# MiniLab.net
KiCad netlist of a schematic drawn in EAGLE
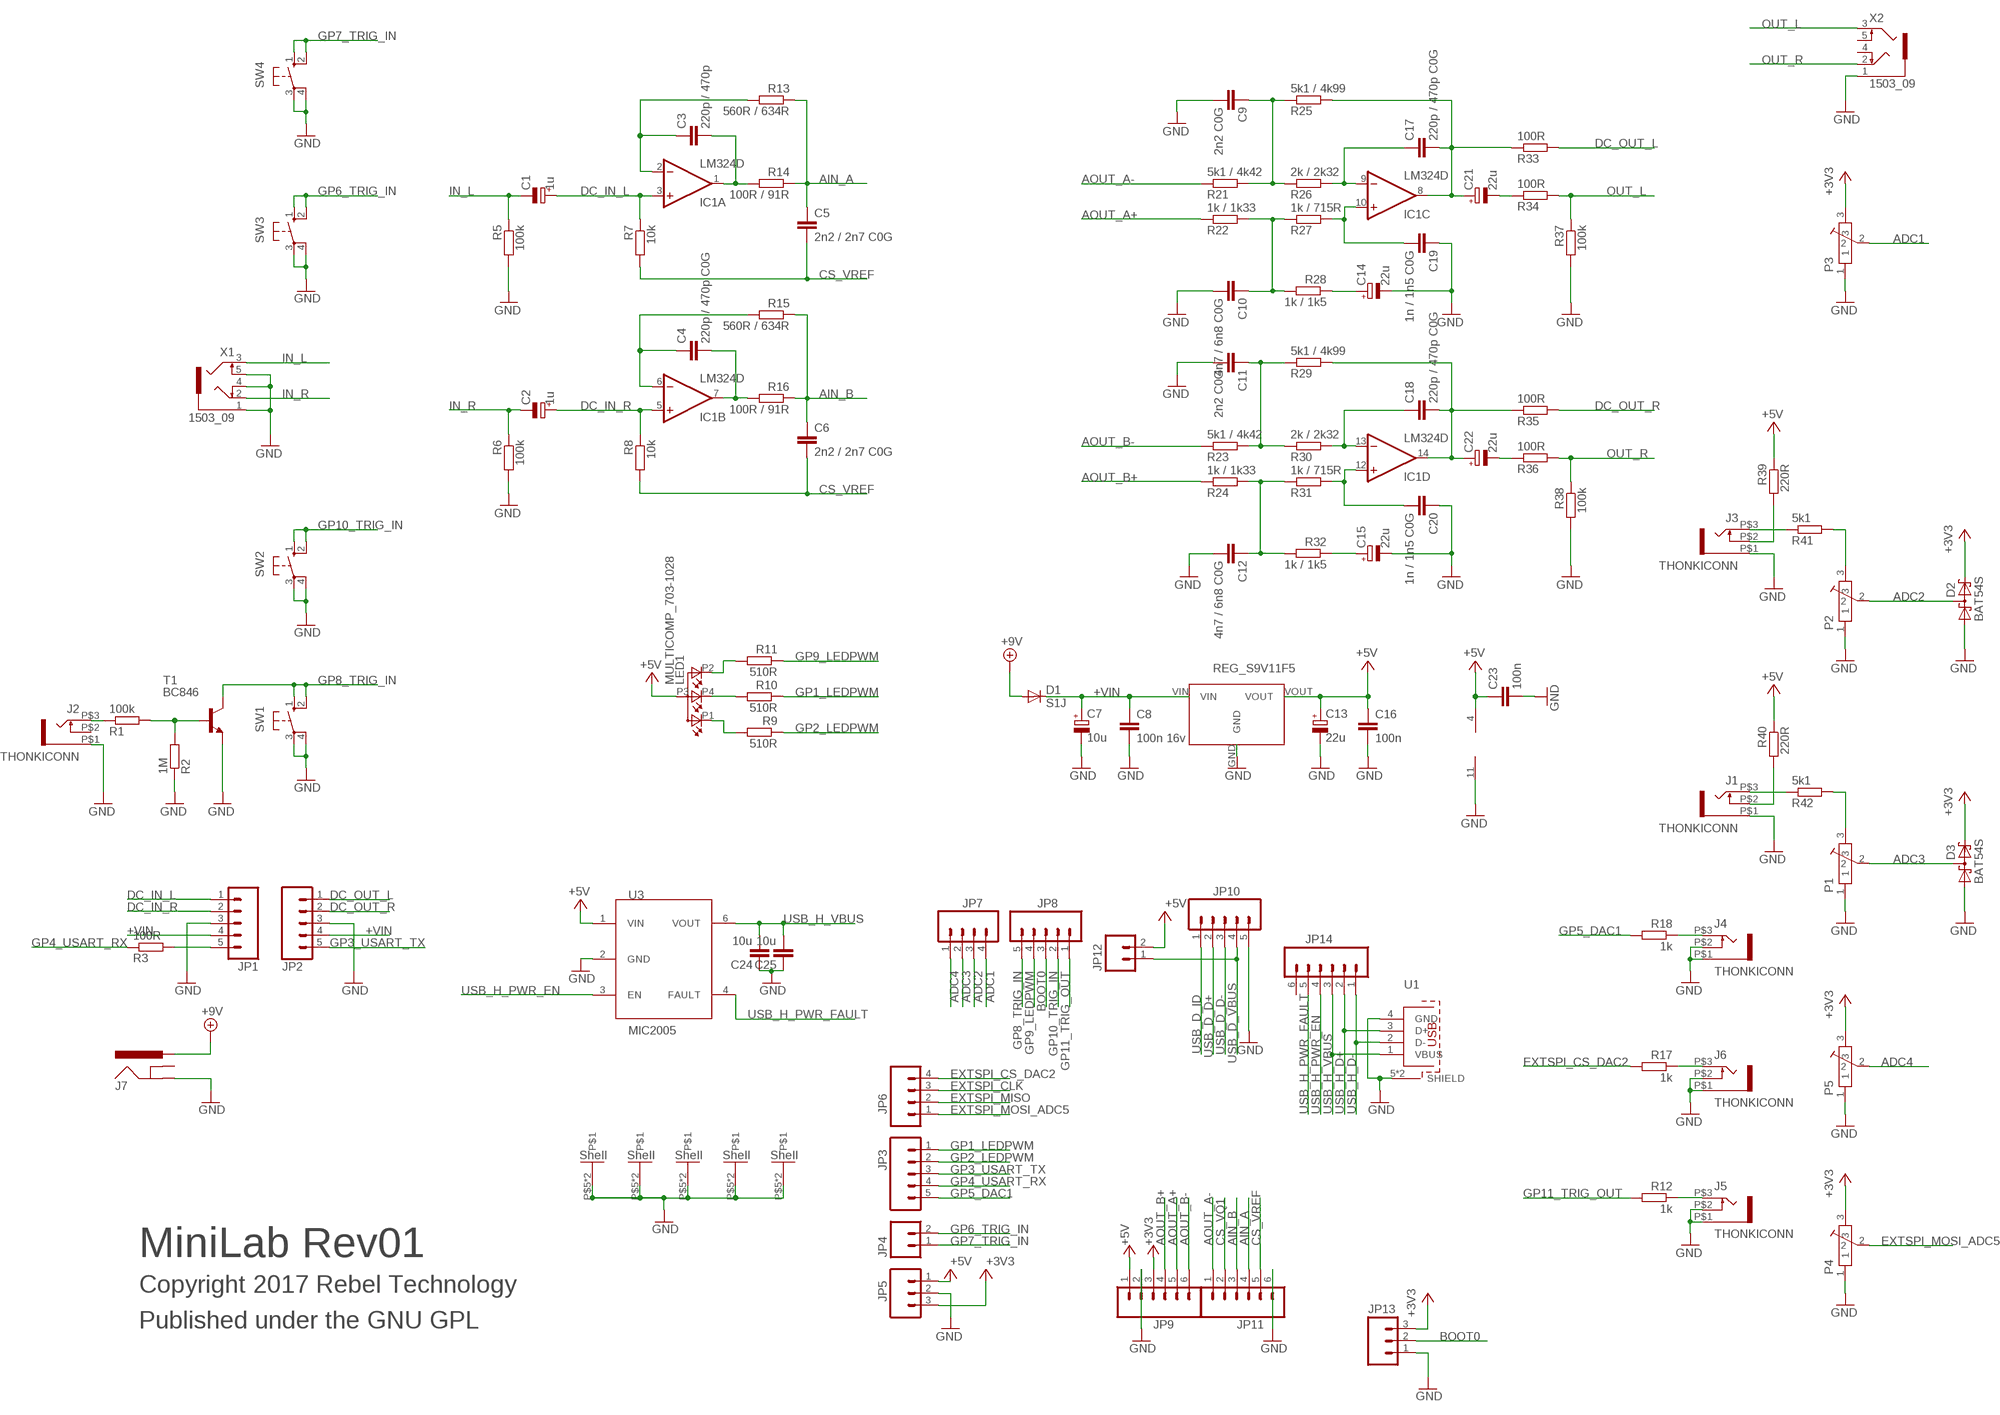
[diagram p0: schematic, sheet 1]

(export (version "E")
  (design (tool "Eeschema 10.0.6"))
  (components
    (comp (ref "C1")
      (value "1u")
      (footprint "eagle-import:153CLV-0405")
      (libsource (lib "eagle-import") (part "CPOL-EU153CLV-0405"))
    )
    (comp (ref "C2")
      (value "1u")
      (footprint "eagle-import:153CLV-0405")
      (libsource (lib "eagle-import") (part "CPOL-EU153CLV-0405"))
    )
    (comp (ref "C3")
      (value "220p / 470p")
      (footprint "eagle-import:C0603")
      (libsource (lib "eagle-import") (part "resistor_C-EUC0603"))
    )
    (comp (ref "C4")
      (value "220p / 470p C0G")
      (footprint "eagle-import:C0603")
      (libsource (lib "eagle-import") (part "resistor_C-EUC0603"))
    )
    (comp (ref "C5")
      (value "2n2 / 2n7 C0G")
      (footprint "eagle-import:C0603")
      (libsource (lib "eagle-import") (part "resistor_C-EUC0603"))
    )
    (comp (ref "C6")
      (value "2n2 / 2n7 C0G")
      (footprint "eagle-import:C0603")
      (libsource (lib "eagle-import") (part "resistor_C-EUC0603"))
    )
    (comp (ref "C7")
      (value "10u")
      (footprint "eagle-import:153CLV-0405")
      (libsource (lib "eagle-import") (part "CPOL-EU153CLV-0405"))
    )
    (comp (ref "C8")
      (value "100n 16v")
      (footprint "eagle-import:C0603")
      (libsource (lib "eagle-import") (part "C-EUC0603"))
    )
    (comp (ref "C9")
      (value "2n2 C0G")
      (footprint "eagle-import:C0603")
      (libsource (lib "eagle-import") (part "resistor_C-EUC0603"))
    )
    (comp (ref "C10")
      (value "4n7 / 6n8 C0G")
      (footprint "eagle-import:C0603")
      (libsource (lib "eagle-import") (part "resistor_C-EUC0603"))
    )
    (comp (ref "C11")
      (value "2n2 C0G")
      (footprint "eagle-import:C0603")
      (libsource (lib "eagle-import") (part "resistor_C-EUC0603"))
    )
    (comp (ref "C12")
      (value "4n7 / 6n8 C0G")
      (footprint "eagle-import:C0603")
      (libsource (lib "eagle-import") (part "resistor_C-EUC0603"))
    )
    (comp (ref "C13")
      (value "22u")
      (footprint "eagle-import:CPOL-5")
      (libsource (lib "eagle-import") (part "CPOL-EU153CLV-0505"))
    )
    (comp (ref "C14")
      (value "22u")
      (footprint "eagle-import:CPOL-5")
      (libsource (lib "eagle-import") (part "CPOL-EU153CLV-0505"))
    )
    (comp (ref "C15")
      (value "22u")
      (footprint "eagle-import:CPOL-5")
      (libsource (lib "eagle-import") (part "CPOL-EU153CLV-0505"))
    )
    (comp (ref "C16")
      (value "100n")
      (footprint "eagle-import:C0603")
      (libsource (lib "eagle-import") (part "C-EUC0603"))
    )
    (comp (ref "C17")
      (value "220p / 470p C0G")
      (footprint "eagle-import:C0603")
      (libsource (lib "eagle-import") (part "resistor_C-EUC0603"))
    )
    (comp (ref "C18")
      (value "220p / 470p C0G")
      (footprint "eagle-import:C0603")
      (libsource (lib "eagle-import") (part "resistor_C-EUC0603"))
    )
    (comp (ref "C19")
      (value "1n / 1n5 C0G")
      (footprint "eagle-import:C0603")
      (libsource (lib "eagle-import") (part "resistor_C-EUC0603"))
    )
    (comp (ref "C20")
      (value "1n / 1n5 C0G")
      (footprint "eagle-import:C0603")
      (libsource (lib "eagle-import") (part "resistor_C-EUC0603"))
    )
    (comp (ref "C21")
      (value "22u")
      (footprint "eagle-import:CPOL-5")
      (libsource (lib "eagle-import") (part "CPOL-EU153CLV-0505"))
    )
    (comp (ref "C22")
      (value "22u")
      (footprint "eagle-import:CPOL-5")
      (libsource (lib "eagle-import") (part "CPOL-EU153CLV-0505"))
    )
    (comp (ref "C23")
      (value "100n")
      (footprint "eagle-import:C0603")
      (libsource (lib "eagle-import") (part "resistor_C-EUC0603"))
    )
    (comp (ref "C24")
      (value "10u")
      (footprint "eagle-import:C0603")
      (libsource (lib "eagle-import") (part "resistor_C-EUC0603"))
    )
    (comp (ref "C25")
      (value "10u")
      (footprint "eagle-import:C0603")
      (libsource (lib "eagle-import") (part "resistor_C-EUC0603"))
    )
    (comp (ref "D1")
      (value "S1J")
      (footprint "eagle-import:SMA-DIODE")
      (libsource (lib "eagle-import") (part "DIODESMA"))
    )
    (comp (ref "D2")
      (value "BAT54S")
      (footprint "eagle-import:SOT23")
      (libsource (lib "eagle-import") (part "BAT54S"))
    )
    (comp (ref "D3")
      (value "BAT54S")
      (footprint "eagle-import:SOT23")
      (libsource (lib "eagle-import") (part "BAT54S"))
    )
    (comp (ref "IC1")
      (value "LM324D")
      (footprint "eagle-import:SO14")
      (libsource (lib "eagle-import") (part "LM324D"))
    )
    (comp (ref "J1")
      (value "THONKICONN")
      (footprint "eagle-import:THONKICONN")
      (libsource (lib "eagle-import") (part "THONKICONN"))
    )
    (comp (ref "J2")
      (value "THONKICONN")
      (footprint "eagle-import:THONKICONN")
      (libsource (lib "eagle-import") (part "THONKICONN"))
    )
    (comp (ref "J3")
      (value "THONKICONN")
      (footprint "eagle-import:THONKICONN")
      (libsource (lib "eagle-import") (part "THONKICONN"))
    )
    (comp (ref "J4")
      (value "THONKICONN")
      (footprint "eagle-import:THONKICONN")
      (libsource (lib "eagle-import") (part "THONKICONN"))
    )
    (comp (ref "J5")
      (value "THONKICONN")
      (footprint "eagle-import:THONKICONN")
      (libsource (lib "eagle-import") (part "THONKICONN"))
    )
    (comp (ref "J6")
      (value "THONKICONN")
      (footprint "eagle-import:THONKICONN")
      (libsource (lib "eagle-import") (part "THONKICONN"))
    )
    (comp (ref "J7")
      (value "POWER_JACKPTH")
      (footprint "eagle-import:POWER_JACK_PTH")
      (libsource (lib "eagle-import") (part "POWER_JACKPTH"))
    )
    (comp (ref "JP1")
      (value "M05PTH")
      (footprint "eagle-import:1X05")
      (libsource (lib "eagle-import") (part "M05PTH"))
    )
    (comp (ref "JP2")
      (value "M05PTH")
      (footprint "eagle-import:1X05")
      (libsource (lib "eagle-import") (part "M05PTH"))
    )
    (comp (ref "JP3")
      (value "M05PTH")
      (footprint "eagle-import:1X05")
      (libsource (lib "eagle-import") (part "M05PTH"))
    )
    (comp (ref "JP4")
      (value "M02PTH")
      (footprint "eagle-import:1X02")
      (libsource (lib "eagle-import") (part "M02PTH"))
    )
    (comp (ref "JP5")
      (value "M03PTH")
      (footprint "eagle-import:1X03")
      (libsource (lib "eagle-import") (part "M03PTH"))
    )
    (comp (ref "JP6")
      (value "M04PTH")
      (footprint "eagle-import:1X04")
      (libsource (lib "eagle-import") (part "M04PTH"))
    )
    (comp (ref "JP7")
      (value "M04PTH")
      (footprint "eagle-import:1X04")
      (libsource (lib "eagle-import") (part "M04PTH"))
    )
    (comp (ref "JP8")
      (value "M05PTH")
      (footprint "eagle-import:1X05")
      (libsource (lib "eagle-import") (part "M05PTH"))
    )
    (comp (ref "JP9")
      (value "M06SIP")
      (footprint "eagle-import:1X06")
      (libsource (lib "eagle-import") (part "M06SIP"))
    )
    (comp (ref "JP10")
      (value "M05PTH")
      (footprint "eagle-import:1X05")
      (libsource (lib "eagle-import") (part "M05PTH"))
    )
    (comp (ref "JP11")
      (value "M06SIP")
      (footprint "eagle-import:1X06")
      (libsource (lib "eagle-import") (part "M06SIP"))
    )
    (comp (ref "JP12")
      (value "M02PTH")
      (footprint "eagle-import:1X02")
      (libsource (lib "eagle-import") (part "M02PTH"))
    )
    (comp (ref "JP13")
      (value "M03PTH")
      (footprint "eagle-import:1X03")
      (libsource (lib "eagle-import") (part "M03PTH"))
    )
    (comp (ref "JP14")
      (value "M06SIP")
      (footprint "eagle-import:1X06")
      (libsource (lib "eagle-import") (part "M06SIP"))
    )
    (comp (ref "LED1")
      (value "MULTICOMP_703-1028")
      (footprint "eagle-import:RGB-LED-703-1028")
      (libsource (lib "eagle-import") (part "MULTICOMP_703-1028"))
    )
    (comp (ref "P1")
      (value "POT-ALPS-RK09L1140")
      (footprint "eagle-import:POT-ALPS-RK09L1140")
      (libsource (lib "eagle-import") (part "POT-ALPS-RK09L1140"))
    )
    (comp (ref "P2")
      (value "POT-ALPS-RK09L1140")
      (footprint "eagle-import:POT-ALPS-RK09L1140")
      (libsource (lib "eagle-import") (part "POT-ALPS-RK09L1140"))
    )
    (comp (ref "P3")
      (value "POT-ALPS-RK09L1140")
      (footprint "eagle-import:POT-ALPS-RK09L1140")
      (libsource (lib "eagle-import") (part "POT-ALPS-RK09L1140"))
    )
    (comp (ref "P4")
      (value "POT-ALPS-RK09L1140")
      (footprint "eagle-import:POT-ALPS-RK09L1140")
      (libsource (lib "eagle-import") (part "POT-ALPS-RK09L1140"))
    )
    (comp (ref "P5")
      (value "POT-ALPS-RK09L1140")
      (footprint "eagle-import:POT-ALPS-RK09L1140")
      (libsource (lib "eagle-import") (part "POT-ALPS-RK09L1140"))
    )
    (comp (ref "R1")
      (value "100k")
      (footprint "eagle-import:0603")
      (libsource (lib "eagle-import") (part "R-EU_0603"))
    )
    (comp (ref "R2")
      (value "1M")
      (footprint "eagle-import:0603")
      (libsource (lib "eagle-import") (part "R-EU_0603"))
    )
    (comp (ref "R3")
      (value "100R")
      (footprint "eagle-import:0603")
      (libsource (lib "eagle-import") (part "R-EU_0603"))
    )
    (comp (ref "R5")
      (value "100k")
      (footprint "eagle-import:0603")
      (libsource (lib "eagle-import") (part "R-EU_0603"))
    )
    (comp (ref "R6")
      (value "100k")
      (footprint "eagle-import:0603")
      (libsource (lib "eagle-import") (part "R-EU_0603"))
    )
    (comp (ref "R7")
      (value "10k")
      (footprint "eagle-import:0603")
      (libsource (lib "eagle-import") (part "R-EU_0603"))
    )
    (comp (ref "R8")
      (value "10k")
      (footprint "eagle-import:0603")
      (libsource (lib "eagle-import") (part "R-EU_0603"))
    )
    (comp (ref "R9")
      (value "510R")
      (footprint "eagle-import:0603")
      (libsource (lib "eagle-import") (part "R-EU_0603"))
    )
    (comp (ref "R10")
      (value "510R")
      (footprint "eagle-import:0603")
      (libsource (lib "eagle-import") (part "R-EU_0603"))
    )
    (comp (ref "R11")
      (value "510R")
      (footprint "eagle-import:0603")
      (libsource (lib "eagle-import") (part "R-EU_0603"))
    )
    (comp (ref "R12")
      (value "1k")
      (footprint "eagle-import:0603")
      (libsource (lib "eagle-import") (part "R-EU_0603"))
    )
    (comp (ref "R13")
      (value "560R / 634R")
      (footprint "eagle-import:0603")
      (libsource (lib "eagle-import") (part "R-EU_0603"))
    )
    (comp (ref "R14")
      (value "100R / 91R")
      (footprint "eagle-import:0603")
      (libsource (lib "eagle-import") (part "R-EU_0603"))
    )
    (comp (ref "R15")
      (value "560R / 634R")
      (footprint "eagle-import:0603")
      (libsource (lib "eagle-import") (part "R-EU_0603"))
    )
    (comp (ref "R16")
      (value "100R / 91R")
      (footprint "eagle-import:0603")
      (libsource (lib "eagle-import") (part "R-EU_0603"))
    )
    (comp (ref "R17")
      (value "1k")
      (footprint "eagle-import:0603")
      (libsource (lib "eagle-import") (part "R-EU_0603"))
    )
    (comp (ref "R18")
      (value "1k")
      (footprint "eagle-import:0603")
      (libsource (lib "eagle-import") (part "R-EU_0603"))
    )
    (comp (ref "R21")
      (value "5k1 / 4k42")
      (footprint "eagle-import:0603")
      (libsource (lib "eagle-import") (part "R-EU_0603"))
    )
    (comp (ref "R22")
      (value "1k / 1k33")
      (footprint "eagle-import:0603")
      (libsource (lib "eagle-import") (part "R-EU_0603"))
    )
    (comp (ref "R23")
      (value "5k1 / 4k42")
      (footprint "eagle-import:0603")
      (libsource (lib "eagle-import") (part "R-EU_0603"))
    )
    (comp (ref "R24")
      (value "1k / 1k33")
      (footprint "eagle-import:0603")
      (libsource (lib "eagle-import") (part "R-EU_0603"))
    )
    (comp (ref "R25")
      (value "5k1 / 4k99")
      (footprint "eagle-import:0603")
      (libsource (lib "eagle-import") (part "R-EU_0603"))
    )
    (comp (ref "R26")
      (value "2k / 2k32")
      (footprint "eagle-import:0603")
      (libsource (lib "eagle-import") (part "R-EU_0603"))
    )
    (comp (ref "R27")
      (value "1k / 715R")
      (footprint "eagle-import:0603")
      (libsource (lib "eagle-import") (part "R-EU_0603"))
    )
    (comp (ref "R28")
      (value "1k / 1k5")
      (footprint "eagle-import:0603")
      (libsource (lib "eagle-import") (part "R-EU_0603"))
    )
    (comp (ref "R29")
      (value "5k1 / 4k99")
      (footprint "eagle-import:0603")
      (libsource (lib "eagle-import") (part "R-EU_0603"))
    )
    (comp (ref "R30")
      (value "2k / 2k32")
      (footprint "eagle-import:0603")
      (libsource (lib "eagle-import") (part "R-EU_0603"))
    )
    (comp (ref "R31")
      (value "1k / 715R")
      (footprint "eagle-import:0603")
      (libsource (lib "eagle-import") (part "R-EU_0603"))
    )
    (comp (ref "R32")
      (value "1k / 1k5")
      (footprint "eagle-import:0603")
      (libsource (lib "eagle-import") (part "R-EU_0603"))
    )
    (comp (ref "R33")
      (value "100R")
      (footprint "eagle-import:0603")
      (libsource (lib "eagle-import") (part "R-EU_0603"))
    )
    (comp (ref "R34")
      (value "100R")
      (footprint "eagle-import:0603")
      (libsource (lib "eagle-import") (part "R-EU_0603"))
    )
    (comp (ref "R35")
      (value "100R")
      (footprint "eagle-import:0603")
      (libsource (lib "eagle-import") (part "R-EU_0603"))
    )
    (comp (ref "R36")
      (value "100R")
      (footprint "eagle-import:0603")
      (libsource (lib "eagle-import") (part "R-EU_0603"))
    )
    (comp (ref "R37")
      (value "100k")
      (footprint "eagle-import:0603")
      (libsource (lib "eagle-import") (part "R-EU_0603"))
    )
    (comp (ref "R38")
      (value "100k")
      (footprint "eagle-import:0603")
      (libsource (lib "eagle-import") (part "R-EU_0603"))
    )
    (comp (ref "R39")
      (value "220R")
      (footprint "eagle-import:0603")
      (libsource (lib "eagle-import") (part "R-EU_0603"))
    )
    (comp (ref "R40")
      (value "220R")
      (footprint "eagle-import:0603")
      (libsource (lib "eagle-import") (part "R-EU_0603"))
    )
    (comp (ref "R41")
      (value "5k1")
      (footprint "eagle-import:0603")
      (libsource (lib "eagle-import") (part "R-EU_0603"))
    )
    (comp (ref "R42")
      (value "5k1")
      (footprint "eagle-import:0603")
      (libsource (lib "eagle-import") (part "R-EU_0603"))
    )
    (comp (ref "SW1")
      (value "10-XX")
      (footprint "eagle-import:B3F-10XX")
      (fields (field (name "MPN") "B3F-1000"))
      (libsource (lib "eagle-import") (part "10-XX"))
    )
    (comp (ref "SW2")
      (value "10-XX")
      (footprint "eagle-import:B3F-10XX")
      (fields (field (name "MPN") "B3F-1000"))
      (libsource (lib "eagle-import") (part "10-XX"))
    )
    (comp (ref "SW3")
      (value "10-XX")
      (footprint "eagle-import:B3F-10XX")
      (fields (field (name "MPN") "B3F-1000"))
      (libsource (lib "eagle-import") (part "10-XX"))
    )
    (comp (ref "SW4")
      (value "10-XX")
      (footprint "eagle-import:B3F-10XX")
      (fields (field (name "MPN") "B3F-1000"))
      (libsource (lib "eagle-import") (part "10-XX"))
    )
    (comp (ref "T1")
      (value "BC846")
      (footprint "eagle-import:SOT23")
      (libsource (lib "eagle-import") (part "BC846"))
    )
    (comp (ref "U1")
      (value "614104190121")
      (footprint "eagle-import:614104190121")
      (libsource (lib "eagle-import") (part "614104190121"))
    )
    (comp (ref "U2")
      (value "REG_S9V11F5")
      (footprint "eagle-import:REG_S9V11F5")
      (libsource (lib "eagle-import") (part "REG_S9V11F5"))
    )
    (comp (ref "U3")
      (value "MIC2005")
      (footprint "eagle-import:SOT23-6")
      (libsource (lib "eagle-import") (part "MIC2005"))
    )
    (comp (ref "X1")
      (value "1503_09")
      (footprint "eagle-import:1503_09")
      (libsource (lib "eagle-import") (part "1503_09"))
    )
    (comp (ref "X2")
      (value "1503_09")
      (footprint "eagle-import:1503_09")
      (libsource (lib "eagle-import") (part "1503_09"))
    )
  )
  (nets
    (net (code "1") (name "+3V3") (class "Default")
      (node (ref "D2") (pin "2") (pinfunction "C2_2") (pintype "passive"))
      (node (ref "D3") (pin "2") (pinfunction "C2_2") (pintype "passive"))
      (node (ref "JP13") (pin "3") (pinfunction "3_3") (pintype "passive"))
      (node (ref "JP5") (pin "3") (pinfunction "3_3") (pintype "passive"))
      (node (ref "JP9") (pin "3") (pinfunction "3_3") (pintype "passive"))
      (node (ref "P3") (pin "3") (pinfunction "3_3") (pintype "bidirectional"))
      (node (ref "P4") (pin "3") (pinfunction "3_3") (pintype "bidirectional"))
      (node (ref "P5") (pin "3") (pinfunction "3_3") (pintype "bidirectional"))
    )
    (net (code "2") (name "+5V") (class "Default")
      (node (ref "C13") (pin "+") (pinfunction "+_+") (pintype "passive"))
      (node (ref "C16") (pin "1") (pinfunction "1_1") (pintype "passive"))
      (node (ref "C23") (pin "1") (pinfunction "1_1") (pintype "passive"))
      (node (ref "IC1") (pin "4") (pinfunction "V+_4") (pintype "power_in"))
      (node (ref "JP12") (pin "2") (pinfunction "2_2") (pintype "passive"))
      (node (ref "JP5") (pin "1") (pinfunction "1_1") (pintype "passive"))
      (node (ref "JP9") (pin "1") (pinfunction "1_1") (pintype "passive"))
      (node (ref "LED1") (pin "P3") (pinfunction "A_P3") (pintype "passive"))
      (node (ref "R39") (pin "1") (pinfunction "1_1") (pintype "passive"))
      (node (ref "R40") (pin "1") (pinfunction "1_1") (pintype "passive"))
      (node (ref "U2") (pin "VOUT") (pinfunction "VOUT_VOUT") (pintype "output"))
      (node (ref "U3") (pin "1") (pinfunction "VIN_1") (pintype "power_in"))
    )
    (net (code "3") (name "+9V") (class "Default")
      (node (ref "D1") (pin "A") (pinfunction "A_A") (pintype "passive"))
      (node (ref "J7") (pin "PWR") (pinfunction "PWR_PWR") (pintype "bidirectional"))
    )
    (net (code "4") (name "/+VIN") (class "Default")
      (node (ref "C7") (pin "+") (pinfunction "+_+") (pintype "passive"))
      (node (ref "C8") (pin "1") (pinfunction "1_1") (pintype "passive"))
      (node (ref "D1") (pin "C") (pinfunction "C_C") (pintype "passive"))
      (node (ref "JP1") (pin "4") (pinfunction "4_4") (pintype "passive"))
      (node (ref "JP2") (pin "4") (pinfunction "4_4") (pintype "passive"))
      (node (ref "U2") (pin "VIN") (pinfunction "VIN_VIN") (pintype "input"))
    )
    (net (code "5") (name "/ADC1") (class "Default")
      (node (ref "JP7") (pin "4") (pinfunction "4_4") (pintype "passive"))
      (node (ref "P3") (pin "2") (pinfunction "2_2") (pintype "bidirectional"))
    )
    (net (code "6") (name "/ADC2") (class "Default")
      (node (ref "D2") (pin "3") (pinfunction "C1A2_3") (pintype "passive"))
      (node (ref "JP7") (pin "3") (pinfunction "3_3") (pintype "passive"))
      (node (ref "P2") (pin "2") (pinfunction "2_2") (pintype "bidirectional"))
    )
    (net (code "7") (name "/ADC3") (class "Default")
      (node (ref "D3") (pin "3") (pinfunction "C1A2_3") (pintype "passive"))
      (node (ref "JP7") (pin "2") (pinfunction "2_2") (pintype "passive"))
      (node (ref "P1") (pin "2") (pinfunction "2_2") (pintype "bidirectional"))
    )
    (net (code "8") (name "/ADC4") (class "Default")
      (node (ref "JP7") (pin "1") (pinfunction "1_1") (pintype "passive"))
      (node (ref "P5") (pin "2") (pinfunction "2_2") (pintype "bidirectional"))
    )
    (net (code "9") (name "/AIN_A") (class "Default")
      (node (ref "C5") (pin "1") (pinfunction "1_1") (pintype "passive"))
      (node (ref "JP11") (pin "4") (pinfunction "4_4") (pintype "passive"))
      (node (ref "R13") (pin "1") (pinfunction "1_1") (pintype "passive"))
      (node (ref "R14") (pin "1") (pinfunction "1_1") (pintype "passive"))
    )
    (net (code "10") (name "/AIN_B") (class "Default")
      (node (ref "C6") (pin "1") (pinfunction "1_1") (pintype "passive"))
      (node (ref "JP11") (pin "3") (pinfunction "3_3") (pintype "passive"))
      (node (ref "R15") (pin "1") (pinfunction "1_1") (pintype "passive"))
      (node (ref "R16") (pin "1") (pinfunction "1_1") (pintype "passive"))
    )
    (net (code "11") (name "/AOUT_A+") (class "Default")
      (node (ref "JP9") (pin "5") (pinfunction "5_5") (pintype "passive"))
      (node (ref "R22") (pin "1") (pinfunction "1_1") (pintype "passive"))
    )
    (net (code "12") (name "/AOUT_A-") (class "Default")
      (node (ref "JP11") (pin "1") (pinfunction "1_1") (pintype "passive"))
      (node (ref "R21") (pin "1") (pinfunction "1_1") (pintype "passive"))
    )
    (net (code "13") (name "/AOUT_B+") (class "Default")
      (node (ref "JP9") (pin "4") (pinfunction "4_4") (pintype "passive"))
      (node (ref "R24") (pin "1") (pinfunction "1_1") (pintype "passive"))
    )
    (net (code "14") (name "/AOUT_B-") (class "Default")
      (node (ref "JP9") (pin "6") (pinfunction "6_6") (pintype "passive"))
      (node (ref "R23") (pin "1") (pinfunction "1_1") (pintype "passive"))
    )
    (net (code "15") (name "/BOOT0") (class "Default")
      (node (ref "JP13") (pin "2") (pinfunction "2_2") (pintype "passive"))
      (node (ref "JP8") (pin "3") (pinfunction "3_3") (pintype "passive"))
    )
    (net (code "16") (name "/CS_VQ1") (class "Default")
      (node (ref "JP11") (pin "2") (pinfunction "2_2") (pintype "passive"))
    )
    (net (code "17") (name "/CS_VREF") (class "Default")
      (node (ref "C5") (pin "2") (pinfunction "2_2") (pintype "passive"))
      (node (ref "C6") (pin "2") (pinfunction "2_2") (pintype "passive"))
      (node (ref "JP11") (pin "5") (pinfunction "5_5") (pintype "passive"))
      (node (ref "R7") (pin "2") (pinfunction "2_2") (pintype "passive"))
      (node (ref "R8") (pin "2") (pinfunction "2_2") (pintype "passive"))
    )
    (net (code "18") (name "/DC_IN_L") (class "Default")
      (node (ref "C1") (pin "+") (pinfunction "+_+") (pintype "passive"))
      (node (ref "IC1") (pin "3") (pinfunction "+IN_3") (pintype "input"))
      (node (ref "JP1") (pin "1") (pinfunction "1_1") (pintype "passive"))
      (node (ref "R7") (pin "1") (pinfunction "1_1") (pintype "passive"))
    )
    (net (code "19") (name "/DC_IN_R") (class "Default")
      (node (ref "C2") (pin "+") (pinfunction "+_+") (pintype "passive"))
      (node (ref "IC1") (pin "5") (pinfunction "+IN_5") (pintype "input"))
      (node (ref "JP1") (pin "2") (pinfunction "2_2") (pintype "passive"))
      (node (ref "R8") (pin "1") (pinfunction "1_1") (pintype "passive"))
    )
    (net (code "20") (name "/DC_OUT_L") (class "Default")
      (node (ref "JP2") (pin "1") (pinfunction "1_1") (pintype "passive"))
      (node (ref "R33") (pin "2") (pinfunction "2_2") (pintype "passive"))
    )
    (net (code "21") (name "/DC_OUT_R") (class "Default")
      (node (ref "JP2") (pin "2") (pinfunction "2_2") (pintype "passive"))
      (node (ref "R35") (pin "2") (pinfunction "2_2") (pintype "passive"))
    )
    (net (code "22") (name "/EXTSPI_CLK") (class "Default")
      (node (ref "JP6") (pin "3") (pinfunction "3_3") (pintype "passive"))
    )
    (net (code "23") (name "/EXTSPI_CS_DAC2") (class "Default")
      (node (ref "JP6") (pin "4") (pinfunction "4_4") (pintype "passive"))
      (node (ref "R17") (pin "2") (pinfunction "2_2") (pintype "passive"))
    )
    (net (code "24") (name "/EXTSPI_MISO") (class "Default")
      (node (ref "JP6") (pin "2") (pinfunction "2_2") (pintype "passive"))
    )
    (net (code "25") (name "/EXTSPI_MOSI_ADC5") (class "Default")
      (node (ref "JP6") (pin "1") (pinfunction "1_1") (pintype "passive"))
      (node (ref "P4") (pin "2") (pinfunction "2_2") (pintype "bidirectional"))
    )
    (net (code "26") (name "/GP1_LEDPWM") (class "Default")
      (node (ref "JP3") (pin "1") (pinfunction "1_1") (pintype "passive"))
      (node (ref "R10") (pin "1") (pinfunction "1_1") (pintype "passive"))
    )
    (net (code "27") (name "/GP2_LEDPWM") (class "Default")
      (node (ref "JP3") (pin "2") (pinfunction "2_2") (pintype "passive"))
      (node (ref "R9") (pin "1") (pinfunction "1_1") (pintype "passive"))
    )
    (net (code "28") (name "/GP3_USART_TX") (class "Default")
      (node (ref "JP2") (pin "5") (pinfunction "5_5") (pintype "passive"))
      (node (ref "JP3") (pin "3") (pinfunction "3_3") (pintype "passive"))
    )
    (net (code "29") (name "/GP4_USART_RX") (class "Default")
      (node (ref "JP3") (pin "4") (pinfunction "4_4") (pintype "passive"))
      (node (ref "R3") (pin "1") (pinfunction "1_1") (pintype "passive"))
    )
    (net (code "30") (name "/GP5_DAC1") (class "Default")
      (node (ref "JP3") (pin "5") (pinfunction "5_5") (pintype "passive"))
      (node (ref "R18") (pin "2") (pinfunction "2_2") (pintype "passive"))
    )
    (net (code "31") (name "/GP6_TRIG_IN") (class "Default")
      (node (ref "JP4") (pin "2") (pinfunction "2_2") (pintype "passive"))
      (node (ref "SW3") (pin "1") (pinfunction "S_1") (pintype "passive"))
      (node (ref "SW3") (pin "2") (pinfunction "S1_2") (pintype "passive"))
    )
    (net (code "32") (name "/GP7_TRIG_IN") (class "Default")
      (node (ref "JP4") (pin "1") (pinfunction "1_1") (pintype "passive"))
      (node (ref "SW4") (pin "1") (pinfunction "S_1") (pintype "passive"))
      (node (ref "SW4") (pin "2") (pinfunction "S1_2") (pintype "passive"))
    )
    (net (code "33") (name "/GP8_TRIG_IN") (class "Default")
      (node (ref "JP8") (pin "5") (pinfunction "5_5") (pintype "passive"))
      (node (ref "SW1") (pin "1") (pinfunction "S_1") (pintype "passive"))
      (node (ref "SW1") (pin "2") (pinfunction "S1_2") (pintype "passive"))
      (node (ref "T1") (pin "3") (pinfunction "C_3") (pintype "passive"))
    )
    (net (code "34") (name "/GP9_LEDPWM") (class "Default")
      (node (ref "JP8") (pin "4") (pinfunction "4_4") (pintype "passive"))
      (node (ref "R11") (pin "1") (pinfunction "1_1") (pintype "passive"))
    )
    (net (code "35") (name "/GP10_TRIG_IN") (class "Default")
      (node (ref "JP8") (pin "2") (pinfunction "2_2") (pintype "passive"))
      (node (ref "SW2") (pin "1") (pinfunction "S_1") (pintype "passive"))
      (node (ref "SW2") (pin "2") (pinfunction "S1_2") (pintype "passive"))
    )
    (net (code "36") (name "/GP11_TRIG_OUT") (class "Default")
      (node (ref "JP8") (pin "1") (pinfunction "1_1") (pintype "passive"))
      (node (ref "R12") (pin "2") (pinfunction "2_2") (pintype "passive"))
    )
    (net (code "37") (name "/IN_L") (class "Default")
      (node (ref "C1") (pin "-") (pinfunction "-_-") (pintype "passive"))
      (node (ref "R5") (pin "1") (pinfunction "1_1") (pintype "passive"))
      (node (ref "X1") (pin "3") (pinfunction "3_3") (pintype "passive"))
    )
    (net (code "38") (name "/IN_R") (class "Default")
      (node (ref "C2") (pin "-") (pinfunction "-_-") (pintype "passive"))
      (node (ref "R6") (pin "1") (pinfunction "1_1") (pintype "passive"))
      (node (ref "X1") (pin "2") (pinfunction "2_2") (pintype "passive"))
    )
    (net (code "39") (name "/OUT_L") (class "Default")
      (node (ref "R34") (pin "2") (pinfunction "2_2") (pintype "passive"))
      (node (ref "R37") (pin "1") (pinfunction "1_1") (pintype "passive"))
      (node (ref "X2") (pin "3") (pinfunction "3_3") (pintype "passive"))
    )
    (net (code "40") (name "/OUT_R") (class "Default")
      (node (ref "R36") (pin "2") (pinfunction "2_2") (pintype "passive"))
      (node (ref "R38") (pin "1") (pinfunction "1_1") (pintype "passive"))
      (node (ref "X2") (pin "2") (pinfunction "2_2") (pintype "passive"))
    )
    (net (code "41") (name "/USB_D_D+") (class "Default")
      (node (ref "JP10") (pin "2") (pinfunction "2_2") (pintype "passive"))
    )
    (net (code "42") (name "/USB_D_D-") (class "Default")
      (node (ref "JP10") (pin "3") (pinfunction "3_3") (pintype "passive"))
    )
    (net (code "43") (name "/USB_D_ID") (class "Default")
      (node (ref "JP10") (pin "1") (pinfunction "1_1") (pintype "passive"))
    )
    (net (code "44") (name "/USB_D_VBUS") (class "Default")
      (node (ref "JP10") (pin "4") (pinfunction "4_4") (pintype "passive"))
      (node (ref "JP12") (pin "1") (pinfunction "1_1") (pintype "passive"))
    )
    (net (code "45") (name "/USB_H_D+") (class "Default")
      (node (ref "JP14") (pin "2") (pinfunction "2_2") (pintype "passive"))
      (node (ref "U1") (pin "3") (pinfunction "D+_3") (pintype "bidirectional"))
    )
    (net (code "46") (name "/USB_H_D-") (class "Default")
      (node (ref "JP14") (pin "1") (pinfunction "1_1") (pintype "passive"))
      (node (ref "U1") (pin "2") (pinfunction "D-_2") (pintype "bidirectional"))
    )
    (net (code "47") (name "/USB_H_PWR_EN") (class "Default")
      (node (ref "JP14") (pin "4") (pinfunction "4_4") (pintype "passive"))
      (node (ref "U3") (pin "3") (pinfunction "EN_3") (pintype "input"))
    )
    (net (code "48") (name "/USB_H_PWR_FAULT") (class "Default")
      (node (ref "JP14") (pin "5") (pinfunction "5_5") (pintype "passive"))
      (node (ref "U3") (pin "4") (pinfunction "FAULT_4") (pintype "output"))
    )
    (net (code "49") (name "/USB_H_VBUS") (class "Default")
      (node (ref "C24") (pin "2") (pinfunction "2_2") (pintype "passive"))
      (node (ref "C25") (pin "2") (pinfunction "2_2") (pintype "passive"))
      (node (ref "JP14") (pin "3") (pinfunction "3_3") (pintype "passive"))
      (node (ref "U1") (pin "1") (pinfunction "VBUS_1") (pintype "bidirectional"))
      (node (ref "U3") (pin "6") (pinfunction "VOUT_6") (pintype "output"))
    )
    (net (code "50") (name "GND") (class "Default")
      (node (ref "C10") (pin "2") (pinfunction "2_2") (pintype "passive"))
      (node (ref "C11") (pin "2") (pinfunction "2_2") (pintype "passive"))
      (node (ref "C12") (pin "2") (pinfunction "2_2") (pintype "passive"))
      (node (ref "C13") (pin "-") (pinfunction "-_-") (pintype "passive"))
      (node (ref "C14") (pin "-") (pinfunction "-_-") (pintype "passive"))
      (node (ref "C15") (pin "-") (pinfunction "-_-") (pintype "passive"))
      (node (ref "C16") (pin "2") (pinfunction "2_2") (pintype "passive"))
      (node (ref "C19") (pin "1") (pinfunction "1_1") (pintype "passive"))
      (node (ref "C20") (pin "1") (pinfunction "1_1") (pintype "passive"))
      (node (ref "C23") (pin "2") (pinfunction "2_2") (pintype "passive"))
      (node (ref "C24") (pin "1") (pinfunction "1_1") (pintype "passive"))
      (node (ref "C25") (pin "1") (pinfunction "1_1") (pintype "passive"))
      (node (ref "C7") (pin "-") (pinfunction "-_-") (pintype "passive"))
      (node (ref "C8") (pin "2") (pinfunction "2_2") (pintype "passive"))
      (node (ref "C9") (pin "2") (pinfunction "2_2") (pintype "passive"))
      (node (ref "D2") (pin "1") (pinfunction "A1_1") (pintype "passive"))
      (node (ref "D3") (pin "1") (pinfunction "A1_1") (pintype "passive"))
      (node (ref "IC1") (pin "11") (pinfunction "V-_11") (pintype "power_in"))
      (node (ref "J1") (pin "P$1") (pinfunction "5_P$1") (pintype "passive"))
      (node (ref "J2") (pin "P$1") (pinfunction "5_P$1") (pintype "passive"))
      (node (ref "J3") (pin "P$1") (pinfunction "5_P$1") (pintype "passive"))
      (node (ref "J4") (pin "P$1") (pinfunction "5_P$1") (pintype "passive"))
      (node (ref "J4") (pin "P$2") (pinfunction "4_P$2") (pintype "passive"))
      (node (ref "J5") (pin "P$1") (pinfunction "5_P$1") (pintype "passive"))
      (node (ref "J5") (pin "P$2") (pinfunction "4_P$2") (pintype "passive"))
      (node (ref "J6") (pin "P$1") (pinfunction "5_P$1") (pintype "passive"))
      (node (ref "J6") (pin "P$2") (pinfunction "4_P$2") (pintype "passive"))
      (node (ref "J7") (pin "GND") (pinfunction "GND_GND") (pintype "bidirectional"))
      (node (ref "JP1") (pin "3") (pinfunction "3_3") (pintype "passive"))
      (node (ref "JP10") (pin "5") (pinfunction "5_5") (pintype "passive"))
      (node (ref "JP11") (pin "6") (pinfunction "6_6") (pintype "passive"))
      (node (ref "JP13") (pin "1") (pinfunction "1_1") (pintype "passive"))
      (node (ref "JP2") (pin "3") (pinfunction "3_3") (pintype "passive"))
      (node (ref "JP5") (pin "2") (pinfunction "2_2") (pintype "passive"))
      (node (ref "JP9") (pin "2") (pinfunction "2_2") (pintype "passive"))
      (node (ref "P1") (pin "1") (pinfunction "1_1") (pintype "bidirectional"))
      (node (ref "P1") (pin "P$5") (pinfunction "P$1_P$5") (pintype "bidirectional"))
      (node (ref "P1") (pin "P$6") (pinfunction "P$1_P$6") (pintype "bidirectional"))
      (node (ref "P2") (pin "1") (pinfunction "1_1") (pintype "bidirectional"))
      (node (ref "P2") (pin "P$5") (pinfunction "P$1_P$5") (pintype "bidirectional"))
      (node (ref "P2") (pin "P$6") (pinfunction "P$1_P$6") (pintype "bidirectional"))
      (node (ref "P3") (pin "1") (pinfunction "1_1") (pintype "bidirectional"))
      (node (ref "P3") (pin "P$5") (pinfunction "P$1_P$5") (pintype "bidirectional"))
      (node (ref "P3") (pin "P$6") (pinfunction "P$1_P$6") (pintype "bidirectional"))
      (node (ref "P4") (pin "1") (pinfunction "1_1") (pintype "bidirectional"))
      (node (ref "P4") (pin "P$5") (pinfunction "P$1_P$5") (pintype "bidirectional"))
      (node (ref "P4") (pin "P$6") (pinfunction "P$1_P$6") (pintype "bidirectional"))
      (node (ref "P5") (pin "1") (pinfunction "1_1") (pintype "bidirectional"))
      (node (ref "P5") (pin "P$5") (pinfunction "P$1_P$5") (pintype "bidirectional"))
      (node (ref "P5") (pin "P$6") (pinfunction "P$1_P$6") (pintype "bidirectional"))
      (node (ref "R2") (pin "1") (pinfunction "1_1") (pintype "passive"))
      (node (ref "R37") (pin "2") (pinfunction "2_2") (pintype "passive"))
      (node (ref "R38") (pin "2") (pinfunction "2_2") (pintype "passive"))
      (node (ref "R5") (pin "2") (pinfunction "2_2") (pintype "passive"))
      (node (ref "R6") (pin "2") (pinfunction "2_2") (pintype "passive"))
      (node (ref "SW1") (pin "3") (pinfunction "P_3") (pintype "passive"))
      (node (ref "SW1") (pin "4") (pinfunction "P1_4") (pintype "passive"))
      (node (ref "SW2") (pin "3") (pinfunction "P_3") (pintype "passive"))
      (node (ref "SW2") (pin "4") (pinfunction "P1_4") (pintype "passive"))
      (node (ref "SW3") (pin "3") (pinfunction "P_3") (pintype "passive"))
      (node (ref "SW3") (pin "4") (pinfunction "P1_4") (pintype "passive"))
      (node (ref "SW4") (pin "3") (pinfunction "P_3") (pintype "passive"))
      (node (ref "SW4") (pin "4") (pinfunction "P1_4") (pintype "passive"))
      (node (ref "T1") (pin "2") (pinfunction "E_2") (pintype "passive"))
      (node (ref "U1") (pin "4") (pinfunction "GND_4") (pintype "bidirectional"))
      (node (ref "U1") (pin "5") (pinfunction "SHIELD_5") (pintype "bidirectional"))
      (node (ref "U1") (pin "6") (pinfunction "SHIELD_6") (pintype "bidirectional"))
      (node (ref "U2") (pin "GND") (pinfunction "GND_GND") (pintype "power_in"))
      (node (ref "U3") (pin "2") (pinfunction "GND_2") (pintype "power_in"))
      (node (ref "X1") (pin "1") (pinfunction "1_1") (pintype "passive"))
      (node (ref "X1") (pin "4") (pinfunction "4_4") (pintype "passive"))
      (node (ref "X1") (pin "5") (pinfunction "5_5") (pintype "passive"))
      (node (ref "X2") (pin "1") (pinfunction "1_1") (pintype "passive"))
    )
    (net (code "51") (name "Net-(C9-Pad1)") (class "Default")
      (node (ref "C9") (pin "1") (pinfunction "1_1") (pintype "passive"))
      (node (ref "R21") (pin "2") (pinfunction "2_2") (pintype "passive"))
      (node (ref "R25") (pin "1") (pinfunction "1_1") (pintype "passive"))
      (node (ref "R26") (pin "1") (pinfunction "1_1") (pintype "passive"))
    )
    (net (code "52") (name "Net-(C10-Pad1)") (class "Default")
      (node (ref "C10") (pin "1") (pinfunction "1_1") (pintype "passive"))
      (node (ref "R22") (pin "2") (pinfunction "2_2") (pintype "passive"))
      (node (ref "R27") (pin "1") (pinfunction "1_1") (pintype "passive"))
      (node (ref "R28") (pin "2") (pinfunction "2_2") (pintype "passive"))
    )
    (net (code "53") (name "Net-(C11-Pad1)") (class "Default")
      (node (ref "C11") (pin "1") (pinfunction "1_1") (pintype "passive"))
      (node (ref "R23") (pin "2") (pinfunction "2_2") (pintype "passive"))
      (node (ref "R29") (pin "1") (pinfunction "1_1") (pintype "passive"))
      (node (ref "R30") (pin "1") (pinfunction "1_1") (pintype "passive"))
    )
    (net (code "54") (name "Net-(C12-Pad1)") (class "Default")
      (node (ref "C12") (pin "1") (pinfunction "1_1") (pintype "passive"))
      (node (ref "R24") (pin "2") (pinfunction "2_2") (pintype "passive"))
      (node (ref "R31") (pin "1") (pinfunction "1_1") (pintype "passive"))
      (node (ref "R32") (pin "2") (pinfunction "2_2") (pintype "passive"))
    )
    (net (code "55") (name "Net-(C14-Pad+)") (class "Default")
      (node (ref "C14") (pin "+") (pinfunction "+_+") (pintype "passive"))
      (node (ref "R28") (pin "1") (pinfunction "1_1") (pintype "passive"))
    )
    (net (code "56") (name "Net-(C15-Pad+)") (class "Default")
      (node (ref "C15") (pin "+") (pinfunction "+_+") (pintype "passive"))
      (node (ref "R32") (pin "1") (pinfunction "1_1") (pintype "passive"))
    )
    (net (code "57") (name "Net-(C21-Pad-)") (class "Default")
      (node (ref "C21") (pin "-") (pinfunction "-_-") (pintype "passive"))
      (node (ref "R34") (pin "1") (pinfunction "1_1") (pintype "passive"))
    )
    (net (code "58") (name "Net-(C22-Pad-)") (class "Default")
      (node (ref "C22") (pin "-") (pinfunction "-_-") (pintype "passive"))
      (node (ref "R36") (pin "1") (pinfunction "1_1") (pintype "passive"))
    )
    (net (code "59") (name "Net-(IC1A--IN)") (class "Default")
      (node (ref "C3") (pin "1") (pinfunction "1_1") (pintype "passive"))
      (node (ref "IC1") (pin "2") (pinfunction "-IN_2") (pintype "input"))
      (node (ref "R13") (pin "2") (pinfunction "2_2") (pintype "passive"))
    )
    (net (code "60") (name "Net-(IC1A-OUT)") (class "Default")
      (node (ref "C3") (pin "2") (pinfunction "2_2") (pintype "passive"))
      (node (ref "IC1") (pin "1") (pinfunction "OUT_1") (pintype "output"))
      (node (ref "R14") (pin "2") (pinfunction "2_2") (pintype "passive"))
    )
    (net (code "61") (name "Net-(IC1B--IN)") (class "Default")
      (node (ref "C4") (pin "1") (pinfunction "1_1") (pintype "passive"))
      (node (ref "IC1") (pin "6") (pinfunction "-IN_6") (pintype "input"))
      (node (ref "R15") (pin "2") (pinfunction "2_2") (pintype "passive"))
    )
    (net (code "62") (name "Net-(IC1B-OUT)") (class "Default")
      (node (ref "C4") (pin "2") (pinfunction "2_2") (pintype "passive"))
      (node (ref "IC1") (pin "7") (pinfunction "OUT_7") (pintype "output"))
      (node (ref "R16") (pin "2") (pinfunction "2_2") (pintype "passive"))
    )
    (net (code "63") (name "Net-(IC1C-+IN)") (class "Default")
      (node (ref "C19") (pin "2") (pinfunction "2_2") (pintype "passive"))
      (node (ref "IC1") (pin "10") (pinfunction "+IN_10") (pintype "input"))
      (node (ref "R27") (pin "2") (pinfunction "2_2") (pintype "passive"))
    )
    (net (code "64") (name "Net-(IC1C--IN)") (class "Default")
      (node (ref "C17") (pin "1") (pinfunction "1_1") (pintype "passive"))
      (node (ref "IC1") (pin "9") (pinfunction "-IN_9") (pintype "input"))
      (node (ref "R26") (pin "2") (pinfunction "2_2") (pintype "passive"))
    )
    (net (code "65") (name "Net-(IC1C-OUT)") (class "Default")
      (node (ref "C17") (pin "2") (pinfunction "2_2") (pintype "passive"))
      (node (ref "C21") (pin "+") (pinfunction "+_+") (pintype "passive"))
      (node (ref "IC1") (pin "8") (pinfunction "OUT_8") (pintype "output"))
      (node (ref "R25") (pin "2") (pinfunction "2_2") (pintype "passive"))
      (node (ref "R33") (pin "1") (pinfunction "1_1") (pintype "passive"))
    )
    (net (code "66") (name "Net-(IC1D-+IN)") (class "Default")
      (node (ref "C20") (pin "2") (pinfunction "2_2") (pintype "passive"))
      (node (ref "IC1") (pin "12") (pinfunction "+IN_12") (pintype "input"))
      (node (ref "R31") (pin "2") (pinfunction "2_2") (pintype "passive"))
    )
    (net (code "67") (name "Net-(IC1D--IN)") (class "Default")
      (node (ref "C18") (pin "1") (pinfunction "1_1") (pintype "passive"))
      (node (ref "IC1") (pin "13") (pinfunction "-IN_13") (pintype "input"))
      (node (ref "R30") (pin "2") (pinfunction "2_2") (pintype "passive"))
    )
    (net (code "68") (name "Net-(IC1D-OUT)") (class "Default")
      (node (ref "C18") (pin "2") (pinfunction "2_2") (pintype "passive"))
      (node (ref "C22") (pin "+") (pinfunction "+_+") (pintype "passive"))
      (node (ref "IC1") (pin "14") (pinfunction "OUT_14") (pintype "output"))
      (node (ref "R29") (pin "2") (pinfunction "2_2") (pintype "passive"))
      (node (ref "R35") (pin "1") (pinfunction "1_1") (pintype "passive"))
    )
    (net (code "69") (name "Net-(J1-3)") (class "Default")
      (node (ref "J1") (pin "P$3") (pinfunction "3_P$3") (pintype "passive"))
      (node (ref "R42") (pin "1") (pinfunction "1_1") (pintype "passive"))
    )
    (net (code "70") (name "Net-(J1-4)") (class "Default")
      (node (ref "J1") (pin "P$2") (pinfunction "4_P$2") (pintype "passive"))
      (node (ref "R40") (pin "2") (pinfunction "2_2") (pintype "passive"))
    )
    (net (code "71") (name "Net-(J2-3)") (class "Default")
      (node (ref "J2") (pin "P$3") (pinfunction "3_P$3") (pintype "passive"))
      (node (ref "R1") (pin "1") (pinfunction "1_1") (pintype "passive"))
    )
    (net (code "72") (name "Net-(J3-3)") (class "Default")
      (node (ref "J3") (pin "P$3") (pinfunction "3_P$3") (pintype "passive"))
      (node (ref "R41") (pin "1") (pinfunction "1_1") (pintype "passive"))
    )
    (net (code "73") (name "Net-(J3-4)") (class "Default")
      (node (ref "J3") (pin "P$2") (pinfunction "4_P$2") (pintype "passive"))
      (node (ref "R39") (pin "2") (pinfunction "2_2") (pintype "passive"))
    )
    (net (code "74") (name "Net-(J4-3)") (class "Default")
      (node (ref "J4") (pin "P$3") (pinfunction "3_P$3") (pintype "passive"))
      (node (ref "R18") (pin "1") (pinfunction "1_1") (pintype "passive"))
    )
    (net (code "75") (name "Net-(J5-3)") (class "Default")
      (node (ref "J5") (pin "P$3") (pinfunction "3_P$3") (pintype "passive"))
      (node (ref "R12") (pin "1") (pinfunction "1_1") (pintype "passive"))
    )
    (net (code "76") (name "Net-(J6-3)") (class "Default")
      (node (ref "J6") (pin "P$3") (pinfunction "3_P$3") (pintype "passive"))
      (node (ref "R17") (pin "1") (pinfunction "1_1") (pintype "passive"))
    )
    (net (code "77") (name "Net-(JP1-Pad5)") (class "Default")
      (node (ref "JP1") (pin "5") (pinfunction "5_5") (pintype "passive"))
      (node (ref "R3") (pin "2") (pinfunction "2_2") (pintype "passive"))
    )
    (net (code "78") (name "Net-(LED1-CBLUE)") (class "Default")
      (node (ref "LED1") (pin "P4") (pinfunction "CBLUE_P4") (pintype "passive"))
      (node (ref "R10") (pin "2") (pinfunction "2_2") (pintype "passive"))
    )
    (net (code "79") (name "Net-(LED1-CGREEN)") (class "Default")
      (node (ref "LED1") (pin "P2") (pinfunction "CGREEN_P2") (pintype "passive"))
      (node (ref "R11") (pin "2") (pinfunction "2_2") (pintype "passive"))
    )
    (net (code "80") (name "Net-(LED1-CRED)") (class "Default")
      (node (ref "LED1") (pin "P1") (pinfunction "CRED_P1") (pintype "passive"))
      (node (ref "R9") (pin "2") (pinfunction "2_2") (pintype "passive"))
    )
    (net (code "81") (name "Net-(P1-Pad3)") (class "Default")
      (node (ref "P1") (pin "3") (pinfunction "3_3") (pintype "bidirectional"))
      (node (ref "R42") (pin "2") (pinfunction "2_2") (pintype "passive"))
    )
    (net (code "82") (name "Net-(P2-Pad3)") (class "Default")
      (node (ref "P2") (pin "3") (pinfunction "3_3") (pintype "bidirectional"))
      (node (ref "R41") (pin "2") (pinfunction "2_2") (pintype "passive"))
    )
    (net (code "83") (name "Net-(T1-B)") (class "Default")
      (node (ref "R1") (pin "2") (pinfunction "2_2") (pintype "passive"))
      (node (ref "R2") (pin "2") (pinfunction "2_2") (pintype "passive"))
      (node (ref "T1") (pin "1") (pinfunction "B_1") (pintype "passive"))
    )
    (net (code "84") (name "unconnected-(J2-4-PadP$2)") (class "Default")
      (node (ref "J2") (pin "P$2") (pinfunction "4_P$2") (pintype "passive"))
    )
    (net (code "85") (name "unconnected-(J7-PadGNDBREAK)") (class "Default")
      (node (ref "J7") (pin "GNDBREAK") (pinfunction "GNDBREAK_GNDBREAK") (pintype "bidirectional"))
    )
    (net (code "86") (name "unconnected-(JP14-Pad6)") (class "Default")
      (node (ref "JP14") (pin "6") (pinfunction "6_6") (pintype "passive"))
    )
    (net (code "87") (name "unconnected-(X2-Pad4)") (class "Default")
      (node (ref "X2") (pin "4") (pinfunction "4_4") (pintype "passive"))
    )
    (net (code "88") (name "unconnected-(X2-Pad5)") (class "Default")
      (node (ref "X2") (pin "5") (pinfunction "5_5") (pintype "passive"))
    )
  )
)
